# 1-Schematic_ESP32_Connecting_PCB.net
KiCad netlist of a schematic drawn in EasyEDA
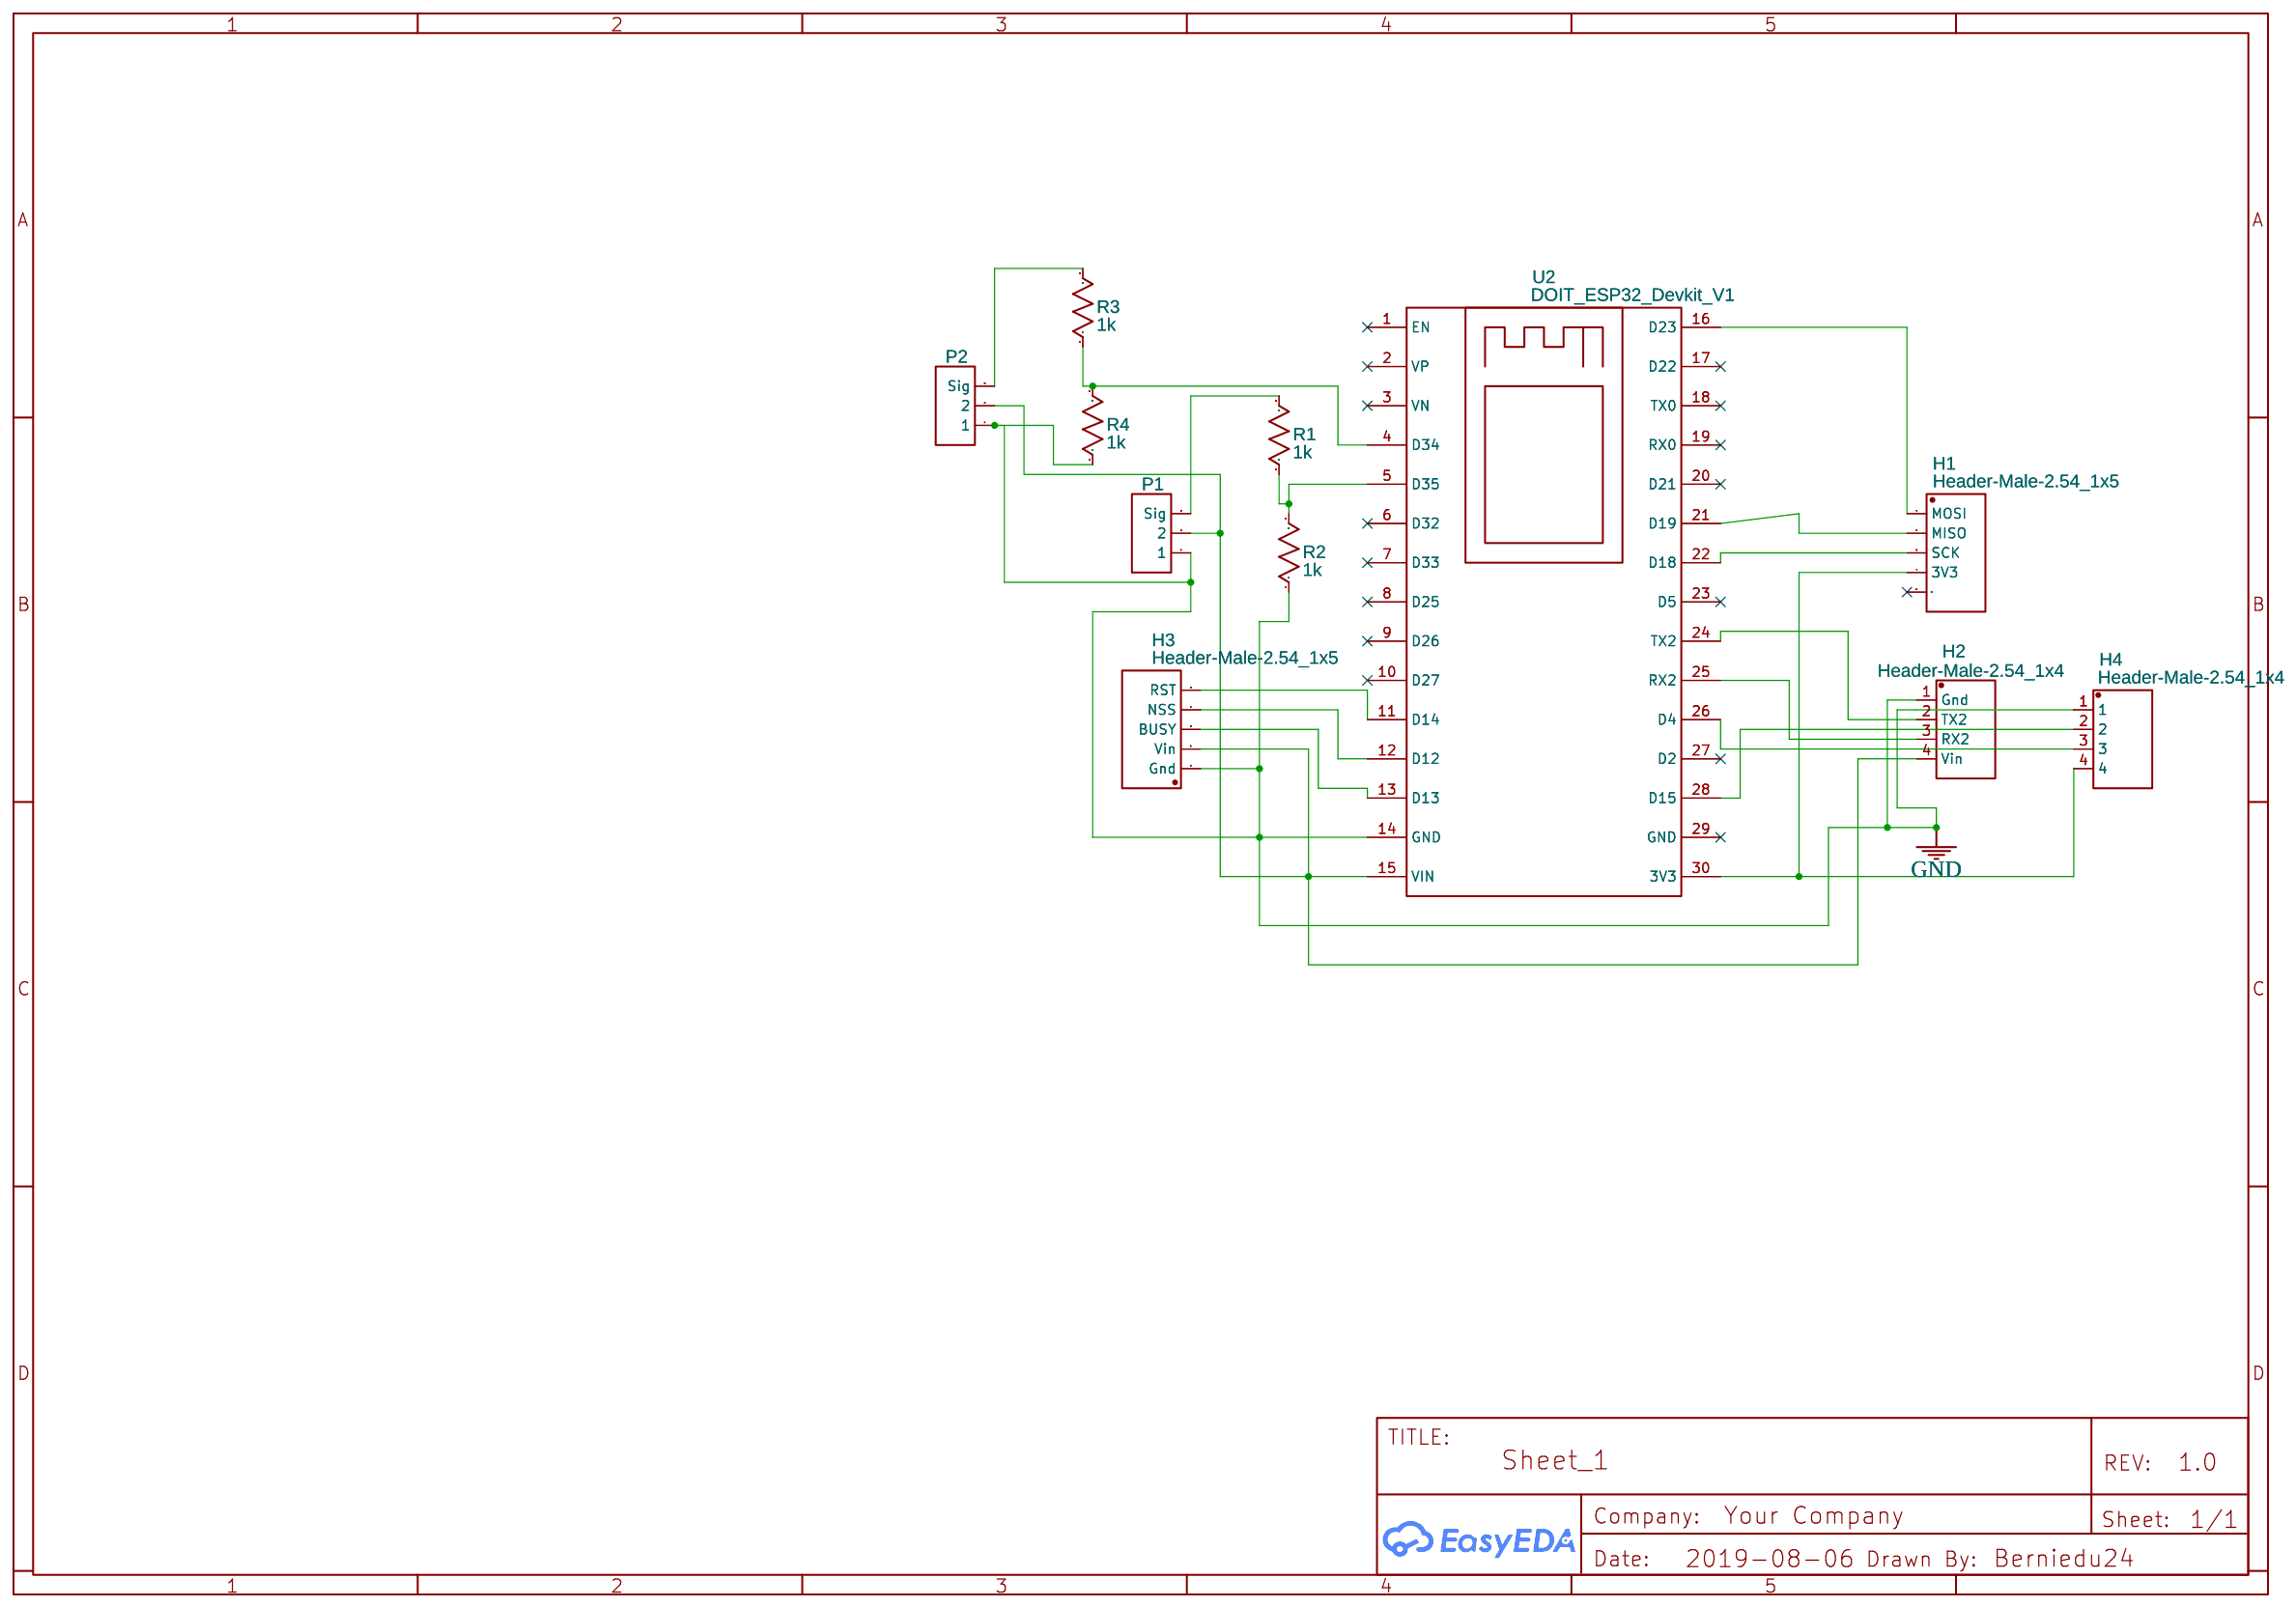
[diagram p0: schematic sheet]

(export (version "E")
  (design (tool "Eeschema 10.0.6"))
  (components
    (comp (ref "H1")
      (value "Header-Male-2.54_1x5")
      (fields
        (field (name "BOM_Manufacturer Part") "210S-1*5P L=11.6MMGold-plated black")
        (field (name "BOM_Supplier Part") "C124379")
      )
      (libsource (lib "") (part "Unknown_985_275"))
    )
    (comp (ref "H2")
      (value "Header-Male-2.54_1x4")
      (fields
        (field (name "BOM_Manufacturer Part") "210S-1*4P L=11.6MMGold-plated black")
        (field (name "BOM_Supplier Part") "C124378")
      )
      (libsource (lib "") (part "Unknown_990_365"))
    )
    (comp (ref "H3")
      (value "Header-Male-2.54_1x5")
      (fields
        (field (name "BOM_Manufacturer Part") "210S-1*5P L=11.6MMGold-plated black")
        (field (name "BOM_Supplier Part") "C124379")
      )
      (libsource (lib "") (part "Unknown_585_365"))
    )
    (comp (ref "H4")
      (value "Header-Male-2.54_1x4")
      (fields
        (field (name "BOM_Manufacturer Part") "210S-1*4P L=11.6MMGold-plated black")
        (field (name "BOM_Supplier Part") "C124378")
      )
      (libsource (lib "") (part "Unknown_1070_370"))
    )
    (comp (ref "P1")
      (value "Header-Male-2.54_1x3")
      (fields
        (field (name "BOM_Manufacturer Part") "Header2.54mm 1*3P")
        (field (name "BOM_Supplier Part") "C49257")
      )
      (libsource (lib "") (part "Unknown_585_265"))
    )
    (comp (ref "P2")
      (value "Header-Male-2.54_1x3")
      (fields
        (field (name "BOM_Manufacturer Part") "Header2.54mm 1*3P")
        (field (name "BOM_Supplier Part") "C49257")
      )
      (libsource (lib "") (part "Unknown_485_200"))
    )
    (comp (ref "R1") (value "1k") (libsource (lib "") (part "Res_AXIAL-0.4(1/4W)_US")))
    (comp (ref "R2") (value "1k") (libsource (lib "") (part "Res_AXIAL-0.4(1/4W)_US")))
    (comp (ref "R3") (value "1k") (libsource (lib "") (part "Res_AXIAL-0.4(1/4W)_US")))
    (comp (ref "R4") (value "1k") (libsource (lib "") (part "Res_AXIAL-0.4(1/4W)_US")))
    (comp (ref "U2")
      (value "DOIT_ESP32_Devkit_V1")
      (fields (field (name "BOM_Manufacturer Part") "ESP32"))
      (libsource (lib "") (part "Unknown_780_300"))
    )
  )
  (nets
    (net (code "1") (name "GND") (class "Default")
      (node (ref "H2") (pin "1") (pinfunction "Gnd_1") (pintype "unspecified"))
      (node (ref "H3") (pin "1") (pinfunction "Gnd_1") (pintype "unspecified"))
      (node (ref "H4") (pin "1") (pinfunction "1_1") (pintype "unspecified"))
      (node (ref "P1") (pin "1") (pinfunction "1_1") (pintype "input"))
      (node (ref "P2") (pin "1") (pinfunction "1_1") (pintype "input"))
      (node (ref "R2") (pin "1") (pinfunction "1_1") (pintype "unspecified"))
      (node (ref "R4") (pin "1") (pinfunction "1_1") (pintype "unspecified"))
      (node (ref "U2") (pin "14") (pinfunction "GND_14") (pintype "unspecified"))
    )
    (net (code "2") (name "Net-(H1-3V3)") (class "Default")
      (node (ref "H1") (pin "4") (pinfunction "3V3_4") (pintype "unspecified"))
      (node (ref "H4") (pin "4") (pinfunction "4_4") (pintype "unspecified"))
      (node (ref "U2") (pin "30") (pinfunction "3V3_30") (pintype "unspecified"))
    )
    (net (code "3") (name "Net-(H1-MISO)") (class "Default")
      (node (ref "H1") (pin "2") (pinfunction "MISO_2") (pintype "unspecified"))
      (node (ref "U2") (pin "21") (pinfunction "D19_21") (pintype "unspecified"))
    )
    (net (code "4") (name "Net-(H1-MOSI)") (class "Default")
      (node (ref "H1") (pin "1") (pinfunction "MOSI_1") (pintype "unspecified"))
      (node (ref "U2") (pin "16") (pinfunction "D23_16") (pintype "unspecified"))
    )
    (net (code "5") (name "Net-(H1-SCK)") (class "Default")
      (node (ref "H1") (pin "3") (pinfunction "SCK_3") (pintype "unspecified"))
      (node (ref "U2") (pin "22") (pinfunction "D18_22") (pintype "unspecified"))
    )
    (net (code "6") (name "Net-(H2-RX2)") (class "Default")
      (node (ref "H2") (pin "3") (pinfunction "RX2_3") (pintype "unspecified"))
      (node (ref "U2") (pin "25") (pinfunction "RX2_25") (pintype "unspecified"))
    )
    (net (code "7") (name "Net-(H2-TX2)") (class "Default")
      (node (ref "H2") (pin "2") (pinfunction "TX2_2") (pintype "unspecified"))
      (node (ref "U2") (pin "24") (pinfunction "TX2_24") (pintype "unspecified"))
    )
    (net (code "8") (name "Net-(H2-Vin)") (class "Default")
      (node (ref "H2") (pin "4") (pinfunction "Vin_4") (pintype "unspecified"))
      (node (ref "H3") (pin "2") (pinfunction "Vin_2") (pintype "unspecified"))
      (node (ref "P1") (pin "2") (pinfunction "2_2") (pintype "input"))
      (node (ref "P2") (pin "2") (pinfunction "2_2") (pintype "input"))
      (node (ref "U2") (pin "15") (pinfunction "VIN_15") (pintype "unspecified"))
    )
    (net (code "9") (name "Net-(H3-BUSY)") (class "Default")
      (node (ref "H3") (pin "3") (pinfunction "BUSY_3") (pintype "unspecified"))
      (node (ref "U2") (pin "13") (pinfunction "D13_13") (pintype "unspecified"))
    )
    (net (code "10") (name "Net-(H3-NSS)") (class "Default")
      (node (ref "H3") (pin "4") (pinfunction "NSS_4") (pintype "unspecified"))
      (node (ref "U2") (pin "12") (pinfunction "D12_12") (pintype "unspecified"))
    )
    (net (code "11") (name "Net-(H3-RST)") (class "Default")
      (node (ref "H3") (pin "5") (pinfunction "RST_5") (pintype "unspecified"))
      (node (ref "U2") (pin "11") (pinfunction "D14_11") (pintype "unspecified"))
    )
    (net (code "12") (name "Net-(P1-Sig)") (class "Default")
      (node (ref "P1") (pin "3") (pinfunction "Sig_3") (pintype "input"))
      (node (ref "R1") (pin "2") (pinfunction "2_2") (pintype "unspecified"))
    )
    (net (code "13") (name "Net-(P2-Sig)") (class "Default")
      (node (ref "P2") (pin "3") (pinfunction "Sig_3") (pintype "input"))
      (node (ref "R3") (pin "2") (pinfunction "2_2") (pintype "unspecified"))
    )
    (net (code "14") (name "Net-(U2-D4)") (class "Default")
      (node (ref "H4") (pin "3") (pinfunction "3_3") (pintype "unspecified"))
      (node (ref "U2") (pin "26") (pinfunction "D4_26") (pintype "unspecified"))
    )
    (net (code "15") (name "Net-(U2-D15)") (class "Default")
      (node (ref "H4") (pin "2") (pinfunction "2_2") (pintype "unspecified"))
      (node (ref "U2") (pin "28") (pinfunction "D15_28") (pintype "unspecified"))
    )
    (net (code "16") (name "Net-(U2-D34)") (class "Default")
      (node (ref "R3") (pin "1") (pinfunction "1_1") (pintype "unspecified"))
      (node (ref "R4") (pin "2") (pinfunction "2_2") (pintype "unspecified"))
      (node (ref "U2") (pin "4") (pinfunction "D34_4") (pintype "unspecified"))
    )
    (net (code "17") (name "Net-(U2-D35)") (class "Default")
      (node (ref "R1") (pin "1") (pinfunction "1_1") (pintype "unspecified"))
      (node (ref "R2") (pin "2") (pinfunction "2_2") (pintype "unspecified"))
      (node (ref "U2") (pin "5") (pinfunction "D35_5") (pintype "unspecified"))
    )
    (net (code "18") (name "unconnected-(H1-NC-Pad5)") (class "Default")
      (node (ref "H1") (pin "5") (pinfunction "NC_5") (pintype "unspecified+no_connect"))
    )
    (net (code "19") (name "unconnected-(U2-D2-Pad27)") (class "Default")
      (node (ref "U2") (pin "27") (pinfunction "D2_27") (pintype "unspecified+no_connect"))
    )
    (net (code "20") (name "unconnected-(U2-D5-Pad23)") (class "Default")
      (node (ref "U2") (pin "23") (pinfunction "D5_23") (pintype "unspecified+no_connect"))
    )
    (net (code "21") (name "unconnected-(U2-D21-Pad20)") (class "Default")
      (node (ref "U2") (pin "20") (pinfunction "D21_20") (pintype "unspecified+no_connect"))
    )
    (net (code "22") (name "unconnected-(U2-D22-Pad17)") (class "Default")
      (node (ref "U2") (pin "17") (pinfunction "D22_17") (pintype "unspecified+no_connect"))
    )
    (net (code "23") (name "unconnected-(U2-D25-Pad8)") (class "Default")
      (node (ref "U2") (pin "8") (pinfunction "D25_8") (pintype "unspecified+no_connect"))
    )
    (net (code "24") (name "unconnected-(U2-D26-Pad9)") (class "Default")
      (node (ref "U2") (pin "9") (pinfunction "D26_9") (pintype "unspecified+no_connect"))
    )
    (net (code "25") (name "unconnected-(U2-D27-Pad10)") (class "Default")
      (node (ref "U2") (pin "10") (pinfunction "D27_10") (pintype "unspecified+no_connect"))
    )
    (net (code "26") (name "unconnected-(U2-D32-Pad6)") (class "Default")
      (node (ref "U2") (pin "6") (pinfunction "D32_6") (pintype "unspecified+no_connect"))
    )
    (net (code "27") (name "unconnected-(U2-D33-Pad7)") (class "Default")
      (node (ref "U2") (pin "7") (pinfunction "D33_7") (pintype "unspecified+no_connect"))
    )
    (net (code "28") (name "unconnected-(U2-EN-Pad1)") (class "Default")
      (node (ref "U2") (pin "1") (pinfunction "EN_1") (pintype "unspecified+no_connect"))
    )
    (net (code "29") (name "unconnected-(U2-GND-Pad29)") (class "Default")
      (node (ref "U2") (pin "29") (pinfunction "GND_29") (pintype "unspecified+no_connect"))
    )
    (net (code "30") (name "unconnected-(U2-RX0-Pad19)") (class "Default")
      (node (ref "U2") (pin "19") (pinfunction "RX0_19") (pintype "unspecified+no_connect"))
    )
    (net (code "31") (name "unconnected-(U2-TX0-Pad18)") (class "Default")
      (node (ref "U2") (pin "18") (pinfunction "TX0_18") (pintype "unspecified+no_connect"))
    )
    (net (code "32") (name "unconnected-(U2-VN-Pad3)") (class "Default")
      (node (ref "U2") (pin "3") (pinfunction "VN_3") (pintype "unspecified+no_connect"))
    )
    (net (code "33") (name "unconnected-(U2-VP-Pad2)") (class "Default")
      (node (ref "U2") (pin "2") (pinfunction "VP_2") (pintype "unspecified+no_connect"))
    )
  )
)
